# VEML6030_Breakout.net
KiCad netlist of a schematic drawn in EAGLE
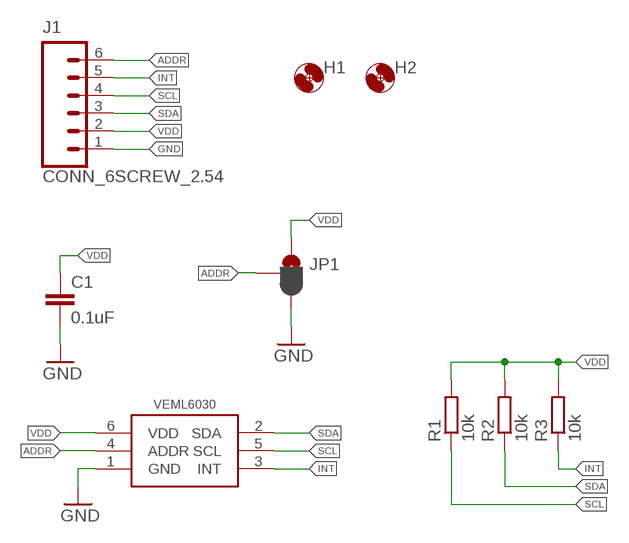
[diagram p0: schematic, sheet 1]

(export (version "E")
  (design (tool "Eeschema 10.0.6"))
  (components
    (comp (ref "C1")
      (value "0.1uF")
      (footprint "eagle-import:C0603")
      (fields (field (name "MF") "Murata") (field (name "MPN") "GCM188R71E104KA57D"))
      (libsource (lib "eagle-import") (part "C-EUC06030.1UF"))
    )
    (comp (ref "H1")
      (value "MOUNTING_HOLE2_NP")
      (footprint "eagle-import:2_56")
      (fields (field (name "MPN") "DNP"))
      (libsource (lib "eagle-import") (part "MOUNTING_HOLE2_NP"))
    )
    (comp (ref "H2")
      (value "MOUNTING_HOLE2_NP")
      (footprint "eagle-import:2_56")
      (fields (field (name "MPN") "DNP"))
      (libsource (lib "eagle-import") (part "MOUNTING_HOLE2_NP"))
    )
    (comp (ref "J1")
      (value "CONN_6SCREW_2.54")
      (footprint "eagle-import:1X06_SCREW")
      (fields (field (name "MF") "OnShore") (field (name "MPN") "OSTVN06A150"))
      (libsource (lib "eagle-import") (part "CONN_6SCREW_2.54"))
    )
    (comp (ref "JP1")
      (value "JUMPER-SMT_3_1-NC_PASTE_SILK")
      (footprint "eagle-import:SMT-JUMPER_3_1-NC_PASTE_SILK")
      (libsource (lib "eagle-import") (part "JUMPER-SMT_3_1-NC_PASTE_SILK"))
    )
    (comp (ref "R1")
      (value "10k")
      (footprint "eagle-import:R0603")
      (fields (field (name "MF") "Yageo") (field (name "MPN") "RC0603FR-0710KL"))
      (libsource (lib "eagle-import") (part "R-EU_R060310K"))
    )
    (comp (ref "R2")
      (value "10k")
      (footprint "eagle-import:R0603")
      (fields (field (name "MF") "Yageo") (field (name "MPN") "RC0603FR-0710KL"))
      (libsource (lib "eagle-import") (part "R-EU_R060310K"))
    )
    (comp (ref "R3")
      (value "10k")
      (footprint "eagle-import:R0603")
      (fields (field (name "MF") "Yageo") (field (name "MPN") "RC0603FR-0710KL"))
      (libsource (lib "eagle-import") (part "R-EU_R060310K"))
    )
    (comp (ref "U1")
      (value "VEML6030")
      (footprint "eagle-import:VEML6030")
      (fields (field (name "MF") "Vishay") (field (name "MPN") "VEML6030-GS15"))
      (libsource (lib "eagle-import") (part "VEML6030"))
    )
  )
  (nets
    (net (code "1") (name "ADDR") (class "Default")
      (node (ref "J1") (pin "6") (pinfunction "6_6") (pintype "passive"))
      (node (ref "JP1") (pin "2") (pinfunction "2_2") (pintype "passive"))
      (node (ref "U1") (pin "4") (pinfunction "ADDR_4") (pintype "input"))
    )
    (net (code "2") (name "GND") (class "Default")
      (node (ref "C1") (pin "2") (pinfunction "2_2") (pintype "passive"))
      (node (ref "J1") (pin "1") (pinfunction "1_1") (pintype "passive"))
      (node (ref "JP1") (pin "3") (pinfunction "3_3") (pintype "passive"))
      (node (ref "U1") (pin "1") (pinfunction "GND_1") (pintype "power_in"))
    )
    (net (code "3") (name "INT") (class "Default")
      (node (ref "J1") (pin "5") (pinfunction "5_5") (pintype "passive"))
      (node (ref "R3") (pin "1") (pinfunction "1_1") (pintype "passive"))
      (node (ref "U1") (pin "3") (pinfunction "INT_3") (pintype "bidirectional"))
    )
    (net (code "4") (name "SCL") (class "Default")
      (node (ref "J1") (pin "4") (pinfunction "4_4") (pintype "passive"))
      (node (ref "R1") (pin "1") (pinfunction "1_1") (pintype "passive"))
      (node (ref "U1") (pin "5") (pinfunction "SCL_5") (pintype "input"))
    )
    (net (code "5") (name "SDA") (class "Default")
      (node (ref "J1") (pin "3") (pinfunction "3_3") (pintype "passive"))
      (node (ref "R2") (pin "1") (pinfunction "1_1") (pintype "passive"))
      (node (ref "U1") (pin "2") (pinfunction "SDA_2") (pintype "bidirectional"))
    )
    (net (code "6") (name "VDD") (class "Default")
      (node (ref "C1") (pin "1") (pinfunction "1_1") (pintype "passive"))
      (node (ref "J1") (pin "2") (pinfunction "2_2") (pintype "passive"))
      (node (ref "JP1") (pin "1") (pinfunction "1_1") (pintype "passive"))
      (node (ref "R1") (pin "2") (pinfunction "2_2") (pintype "passive"))
      (node (ref "R2") (pin "2") (pinfunction "2_2") (pintype "passive"))
      (node (ref "R3") (pin "2") (pinfunction "2_2") (pintype "passive"))
      (node (ref "U1") (pin "6") (pinfunction "VDD_6") (pintype "power_in"))
    )
  )
)
